# MK64.net
KiCad netlist of a schematic drawn in Altium Designer
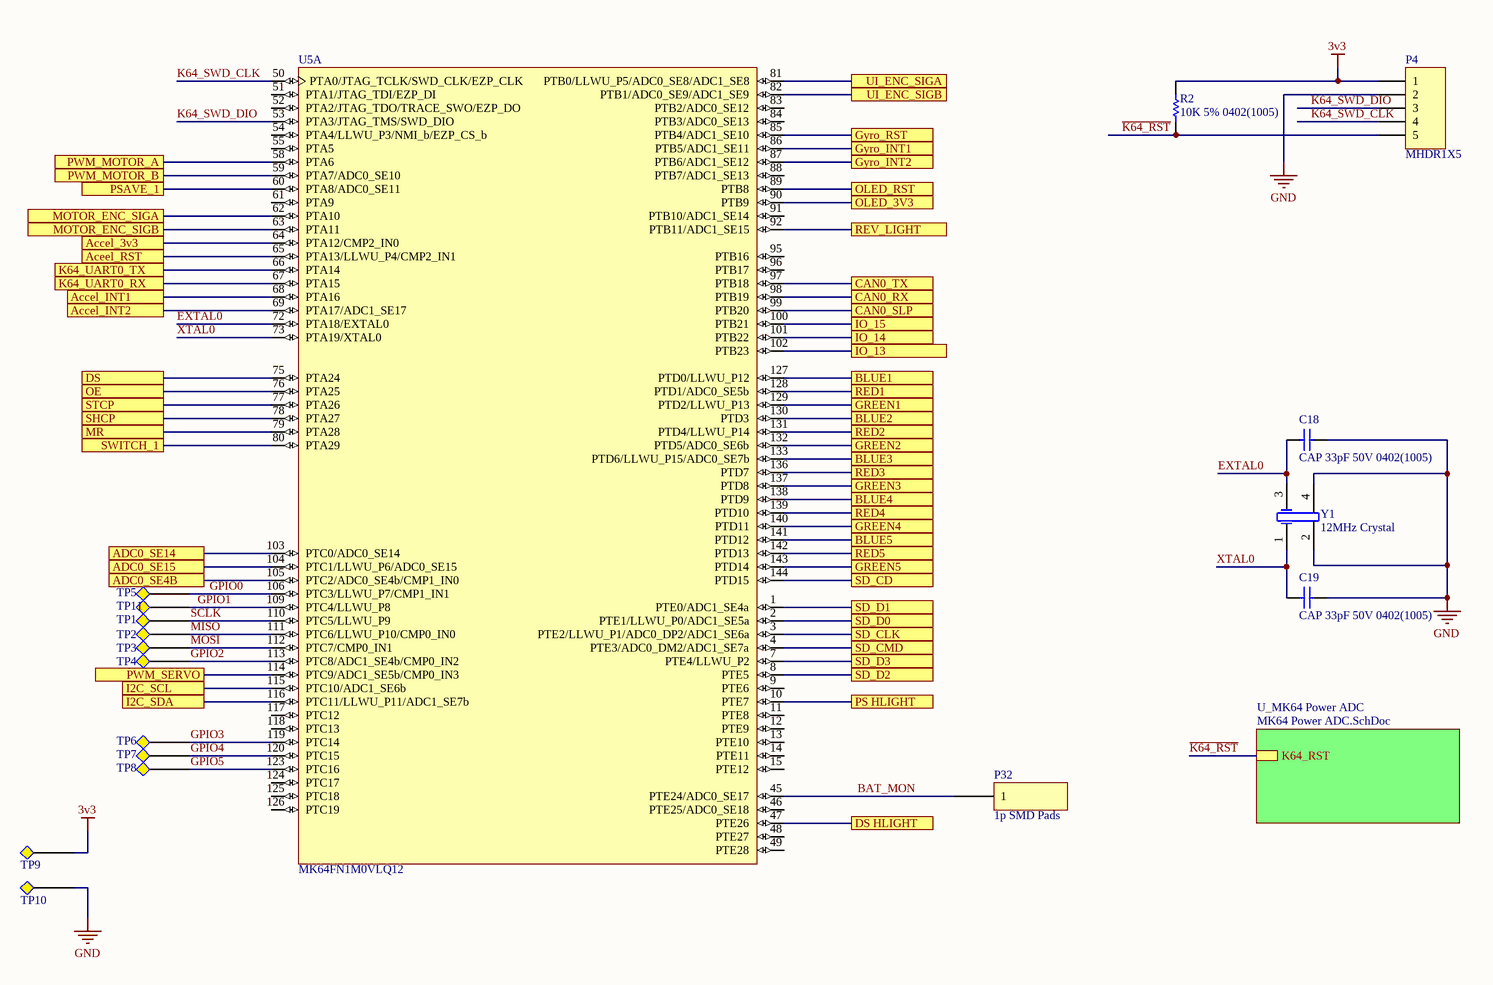
[diagram p0: MK64.SchDoc]

(export (version "E")
  (design (tool "Eeschema 10.0.6"))
  (components
    (comp (ref "C18")
      (value "CAP 33pF 50V 0402(1005)")
      (footprint "CAPC0402(1005)60_N")
      (description "CAP 33pF 50V ±5% 0402 (1005 Metric) Thickness 0.6mm SMD")
      (fields (field (name "TOLERANCE") "Â±5%"))
      (libsource (lib "Altium Content Vault") (part "CAP"))
    )
    (comp (ref "C19")
      (value "CAP 33pF 50V 0402(1005)")
      (footprint "CAPC0402(1005)60_N")
      (description "CAP 33pF 50V ±5% 0402 (1005 Metric) Thickness 0.6mm SMD")
      (fields (field (name "TOLERANCE") "Â±5%"))
      (libsource (lib "Altium Content Vault") (part "CAP"))
    )
    (comp (ref "P4")
      (value "MHDR1X5")
      (footprint "MHDR1X5")
      (description "Header, 5-Pin")
      (fields (field (name "PUBLISHER") "Altium Limited"))
      (libsource (lib "Miscellaneous Connectors") (part "MHDR1X5"))
    )
    (comp (ref "P32")
      (value "1p SMD Pads")
      (footprint "1p SMD pad")
      (libsource (lib "parts") (part "1p SMD"))
    )
    (comp (ref "R2")
      (value "10K 5% 0402(1005)")
      (footprint "RESC0402(1005)_N")
      (description "10K 0.063W 5% 0402 (1005 Metric)  SMD")
      (fields (field (name "TOLERANCE") "5 %") (field (name "POWER") "0.063 W"))
      (libsource (lib "Altium Content Vault") (part "RES"))
    )
    (comp (ref "TP1") (value "Test Point") (footprint "TP") (libsource (lib "parts") (part "TP")))
    (comp (ref "TP2") (value "Test Point") (footprint "TP") (libsource (lib "parts") (part "TP")))
    (comp (ref "TP3") (value "Test Point") (footprint "TP") (libsource (lib "parts") (part "TP")))
    (comp (ref "TP4") (value "Test Point") (footprint "TP") (libsource (lib "parts") (part "TP")))
    (comp (ref "TP5") (value "Test Point") (footprint "TP") (libsource (lib "parts") (part "TP")))
    (comp (ref "TP6") (value "Test Point") (footprint "TP") (libsource (lib "parts") (part "TP")))
    (comp (ref "TP7") (value "Test Point") (footprint "TP") (libsource (lib "parts") (part "TP")))
    (comp (ref "TP8") (value "Test Point") (footprint "TP") (libsource (lib "parts") (part "TP")))
    (comp (ref "TP9") (value "Test Point") (footprint "TP") (libsource (lib "parts") (part "TP")))
    (comp (ref "TP10") (value "Test Point") (footprint "TP") (libsource (lib "parts") (part "TP")))
    (comp (ref "TP11") (value "Test Point") (footprint "TP") (libsource (lib "parts") (part "TP")))
    (comp (ref "U5")
      (value "MK64FN1M0VLQ12")
      (footprint "918-03_N")
      (fields (field (name "MANUFACTURER") "Freescale Semiconductor"))
      (libsource (lib "Altium Content Vault") (part "FRES-MK64FX512VLQ12-144"))
    )
    (comp (ref "Y1")
      (value "12MHz Crystal")
      (footprint "DFN155P250X80-4N")
      (description "CRYSTAL 12.0000MHZ 20PF SMD 3.20x2.50")
      (fields (field (name "PUBLISHER") "Altium Limited"))
      (libsource (lib "parts") (part "403C11E16M00000"))
    )
  )
  (nets
    (net (code "1") (name "/ADC0_SE4B") (class "Default")
      (node (ref "U5") (pin "105") (pinfunction "PTC2/ADC0_SE4b/CMP1_IN0_105") (pintype "bidirectional"))
    )
    (net (code "2") (name "/ADC0_SE14") (class "Default")
      (node (ref "U5") (pin "103") (pinfunction "PTC0/ADC0_SE14_103") (pintype "bidirectional"))
    )
    (net (code "3") (name "/ADC0_SE15") (class "Default")
      (node (ref "U5") (pin "104") (pinfunction "PTC1/LLWU_P6/ADC0_SE15_104") (pintype "bidirectional"))
    )
    (net (code "4") (name "/Accel_3v3") (class "Default")
      (node (ref "U5") (pin "64") (pinfunction "PTA12/CMP2_IN0_64") (pintype "bidirectional"))
    )
    (net (code "5") (name "/Accel_INT1") (class "Default")
      (node (ref "U5") (pin "68") (pinfunction "PTA16_68") (pintype "bidirectional"))
    )
    (net (code "6") (name "/Accel_INT2") (class "Default")
      (node (ref "U5") (pin "69") (pinfunction "PTA17/ADC1_SE17_69") (pintype "bidirectional"))
    )
    (net (code "7") (name "/Aceel_RST") (class "Default")
      (node (ref "U5") (pin "65") (pinfunction "PTA13/LLWU_P4/CMP2_IN1_65") (pintype "bidirectional"))
    )
    (net (code "8") (name "/BAT_MON") (class "Default")
      (node (ref "P32") (pin "1") (pinfunction "1_1") (pintype "passive"))
      (node (ref "U5") (pin "45") (pinfunction "PTE24/ADC0_SE17_45") (pintype "bidirectional"))
    )
    (net (code "9") (name "/BLUE1") (class "Default")
      (node (ref "U5") (pin "127") (pinfunction "PTD0/LLWU_P12_127") (pintype "bidirectional"))
    )
    (net (code "10") (name "/BLUE2") (class "Default")
      (node (ref "U5") (pin "130") (pinfunction "PTD3_130") (pintype "bidirectional"))
    )
    (net (code "11") (name "/BLUE3") (class "Default")
      (node (ref "U5") (pin "133") (pinfunction "PTD6/LLWU_P15/ADC0_SE7b_133") (pintype "bidirectional"))
    )
    (net (code "12") (name "/BLUE4") (class "Default")
      (node (ref "U5") (pin "138") (pinfunction "PTD9_138") (pintype "bidirectional"))
    )
    (net (code "13") (name "/BLUE5") (class "Default")
      (node (ref "U5") (pin "141") (pinfunction "PTD12_141") (pintype "bidirectional"))
    )
    (net (code "14") (name "/CAN0_RX") (class "Default")
      (node (ref "U5") (pin "98") (pinfunction "PTB19_98") (pintype "bidirectional"))
    )
    (net (code "15") (name "/CAN0_SLP") (class "Default")
      (node (ref "U5") (pin "99") (pinfunction "PTB20_99") (pintype "bidirectional"))
    )
    (net (code "16") (name "/CAN0_TX") (class "Default")
      (node (ref "U5") (pin "97") (pinfunction "PTB18_97") (pintype "bidirectional"))
    )
    (net (code "17") (name "/DS") (class "Default")
      (node (ref "U5") (pin "75") (pinfunction "PTA24_75") (pintype "bidirectional"))
    )
    (net (code "18") (name "/DS HLIGHT") (class "Default")
      (node (ref "U5") (pin "47") (pinfunction "PTE26_47") (pintype "bidirectional"))
    )
    (net (code "19") (name "/EXTAL0") (class "Default")
      (node (ref "C18") (pin "1") (pinfunction "1_1") (pintype "passive"))
      (node (ref "U5") (pin "72") (pinfunction "PTA18/EXTAL0_72") (pintype "bidirectional"))
      (node (ref "Y1") (pin "3") (pinfunction "OSC2_3") (pintype "passive"))
    )
    (net (code "20") (name "/GPIO0") (class "Default")
      (node (ref "TP5") (pin "1") (pinfunction "1_1") (pintype "passive"))
      (node (ref "U5") (pin "106") (pinfunction "PTC3/LLWU_P7/CMP1_IN1_106") (pintype "bidirectional"))
    )
    (net (code "21") (name "/GPIO1") (class "Default")
      (node (ref "TP11") (pin "1") (pinfunction "1_1") (pintype "passive"))
      (node (ref "U5") (pin "109") (pinfunction "PTC4/LLWU_P8_109") (pintype "bidirectional"))
    )
    (net (code "22") (name "/GPIO2") (class "Default")
      (node (ref "TP4") (pin "1") (pinfunction "1_1") (pintype "passive"))
      (node (ref "U5") (pin "113") (pinfunction "PTC8/ADC1_SE4b/CMP0_IN2_113") (pintype "bidirectional"))
    )
    (net (code "23") (name "/GPIO3") (class "Default")
      (node (ref "TP6") (pin "1") (pinfunction "1_1") (pintype "passive"))
      (node (ref "U5") (pin "119") (pinfunction "PTC14_119") (pintype "bidirectional"))
    )
    (net (code "24") (name "/GPIO4") (class "Default")
      (node (ref "TP7") (pin "1") (pinfunction "1_1") (pintype "passive"))
      (node (ref "U5") (pin "120") (pinfunction "PTC15_120") (pintype "bidirectional"))
    )
    (net (code "25") (name "/GPIO5") (class "Default")
      (node (ref "TP8") (pin "1") (pinfunction "1_1") (pintype "passive"))
      (node (ref "U5") (pin "123") (pinfunction "PTC16_123") (pintype "bidirectional"))
    )
    (net (code "26") (name "/GREEN1") (class "Default")
      (node (ref "U5") (pin "129") (pinfunction "PTD2/LLWU_P13_129") (pintype "bidirectional"))
    )
    (net (code "27") (name "/GREEN2") (class "Default")
      (node (ref "U5") (pin "132") (pinfunction "PTD5/ADC0_SE6b_132") (pintype "bidirectional"))
    )
    (net (code "28") (name "/GREEN3") (class "Default")
      (node (ref "U5") (pin "137") (pinfunction "PTD8_137") (pintype "bidirectional"))
    )
    (net (code "29") (name "/GREEN4") (class "Default")
      (node (ref "U5") (pin "140") (pinfunction "PTD11_140") (pintype "bidirectional"))
    )
    (net (code "30") (name "/GREEN5") (class "Default")
      (node (ref "U5") (pin "143") (pinfunction "PTD14_143") (pintype "bidirectional"))
    )
    (net (code "31") (name "/Gyro_INT1") (class "Default")
      (node (ref "U5") (pin "86") (pinfunction "PTB5/ADC1_SE11_86") (pintype "bidirectional"))
    )
    (net (code "32") (name "/Gyro_INT2") (class "Default")
      (node (ref "U5") (pin "87") (pinfunction "PTB6/ADC1_SE12_87") (pintype "bidirectional"))
    )
    (net (code "33") (name "/Gyro_RST") (class "Default")
      (node (ref "U5") (pin "85") (pinfunction "PTB4/ADC1_SE10_85") (pintype "bidirectional"))
    )
    (net (code "34") (name "/I2C_SCL") (class "Default")
      (node (ref "U5") (pin "115") (pinfunction "PTC10/ADC1_SE6b_115") (pintype "bidirectional"))
    )
    (net (code "35") (name "/I2C_SDA") (class "Default")
      (node (ref "U5") (pin "116") (pinfunction "PTC11/LLWU_P11/ADC1_SE7b_116") (pintype "bidirectional"))
    )
    (net (code "36") (name "/IO_13") (class "Default")
      (node (ref "U5") (pin "102") (pinfunction "PTB23_102") (pintype "bidirectional"))
    )
    (net (code "37") (name "/IO_14") (class "Default")
      (node (ref "U5") (pin "101") (pinfunction "PTB22_101") (pintype "bidirectional"))
    )
    (net (code "38") (name "/IO_15") (class "Default")
      (node (ref "U5") (pin "100") (pinfunction "PTB21_100") (pintype "bidirectional"))
    )
    (net (code "39") (name "/K64_RST") (class "Default")
      (node (ref "P4") (pin "5") (pinfunction "5_5") (pintype "passive"))
      (node (ref "R2") (pin "1") (pinfunction "1_1") (pintype "passive"))
    )
    (net (code "40") (name "/K64_SWD_CLK") (class "Default")
      (node (ref "P4") (pin "4") (pinfunction "4_4") (pintype "passive"))
      (node (ref "U5") (pin "50") (pinfunction "PTA0/JTAG_TCLK/SWD_CLK/EZP_CLK_50") (pintype "bidirectional"))
    )
    (net (code "41") (name "/K64_SWD_DIO") (class "Default")
      (node (ref "P4") (pin "3") (pinfunction "3_3") (pintype "passive"))
      (node (ref "U5") (pin "53") (pinfunction "PTA3/JTAG_TMS/SWD_DIO_53") (pintype "bidirectional"))
    )
    (net (code "42") (name "/K64_UART0_RX") (class "Default")
      (node (ref "U5") (pin "67") (pinfunction "PTA15_67") (pintype "bidirectional"))
    )
    (net (code "43") (name "/K64_UART0_TX") (class "Default")
      (node (ref "U5") (pin "66") (pinfunction "PTA14_66") (pintype "bidirectional"))
    )
    (net (code "44") (name "/MISO") (class "Default")
      (node (ref "TP2") (pin "1") (pinfunction "1_1") (pintype "passive"))
      (node (ref "U5") (pin "111") (pinfunction "PTC6/LLWU_P10/CMP0_IN0_111") (pintype "bidirectional"))
    )
    (net (code "45") (name "/MOSI") (class "Default")
      (node (ref "TP3") (pin "1") (pinfunction "1_1") (pintype "passive"))
      (node (ref "U5") (pin "112") (pinfunction "PTC7/CMP0_IN1_112") (pintype "bidirectional"))
    )
    (net (code "46") (name "/MOTOR_ENC_SIGA") (class "Default")
      (node (ref "U5") (pin "62") (pinfunction "PTA10_62") (pintype "bidirectional"))
    )
    (net (code "47") (name "/MOTOR_ENC_SIGB") (class "Default")
      (node (ref "U5") (pin "63") (pinfunction "PTA11_63") (pintype "bidirectional"))
    )
    (net (code "48") (name "/MR") (class "Default")
      (node (ref "U5") (pin "79") (pinfunction "PTA28_79") (pintype "bidirectional"))
    )
    (net (code "49") (name "/OE") (class "Default")
      (node (ref "U5") (pin "76") (pinfunction "PTA25_76") (pintype "bidirectional"))
    )
    (net (code "50") (name "/OLED_3V3") (class "Default")
      (node (ref "U5") (pin "90") (pinfunction "PTB9_90") (pintype "bidirectional"))
    )
    (net (code "51") (name "/OLED_RST") (class "Default")
      (node (ref "U5") (pin "89") (pinfunction "PTB8_89") (pintype "bidirectional"))
    )
    (net (code "52") (name "/PS HLIGHT") (class "Default")
      (node (ref "U5") (pin "10") (pinfunction "PTE7_10") (pintype "bidirectional"))
    )
    (net (code "53") (name "/PSAVE_1") (class "Default")
      (node (ref "U5") (pin "60") (pinfunction "PTA8/ADC0_SE11_60") (pintype "bidirectional"))
    )
    (net (code "54") (name "/PWM_MOTOR_A") (class "Default")
      (node (ref "U5") (pin "58") (pinfunction "PTA6_58") (pintype "bidirectional"))
    )
    (net (code "55") (name "/PWM_MOTOR_B") (class "Default")
      (node (ref "U5") (pin "59") (pinfunction "PTA7/ADC0_SE10_59") (pintype "bidirectional"))
    )
    (net (code "56") (name "/PWM_SERVO") (class "Default")
      (node (ref "U5") (pin "114") (pinfunction "PTC9/ADC1_SE5b/CMP0_IN3_114") (pintype "bidirectional"))
    )
    (net (code "57") (name "/RED1") (class "Default")
      (node (ref "U5") (pin "128") (pinfunction "PTD1/ADC0_SE5b_128") (pintype "bidirectional"))
    )
    (net (code "58") (name "/RED2") (class "Default")
      (node (ref "U5") (pin "131") (pinfunction "PTD4/LLWU_P14_131") (pintype "bidirectional"))
    )
    (net (code "59") (name "/RED3") (class "Default")
      (node (ref "U5") (pin "136") (pinfunction "PTD7_136") (pintype "bidirectional"))
    )
    (net (code "60") (name "/RED4") (class "Default")
      (node (ref "U5") (pin "139") (pinfunction "PTD10_139") (pintype "bidirectional"))
    )
    (net (code "61") (name "/RED5") (class "Default")
      (node (ref "U5") (pin "142") (pinfunction "PTD13_142") (pintype "bidirectional"))
    )
    (net (code "62") (name "/REV_LIGHT") (class "Default")
      (node (ref "U5") (pin "92") (pinfunction "PTB11/ADC1_SE15_92") (pintype "bidirectional"))
    )
    (net (code "63") (name "/SCLK") (class "Default")
      (node (ref "TP1") (pin "1") (pinfunction "1_1") (pintype "passive"))
      (node (ref "U5") (pin "110") (pinfunction "PTC5/LLWU_P9_110") (pintype "bidirectional"))
    )
    (net (code "64") (name "/SD_CD") (class "Default")
      (node (ref "U5") (pin "144") (pinfunction "PTD15_144") (pintype "bidirectional"))
    )
    (net (code "65") (name "/SD_CLK") (class "Default")
      (node (ref "U5") (pin "3") (pinfunction "PTE2/LLWU_P1/ADC0_DP2/ADC1_SE6a_3") (pintype "bidirectional"))
    )
    (net (code "66") (name "/SD_CMD") (class "Default")
      (node (ref "U5") (pin "4") (pinfunction "PTE3/ADC0_DM2/ADC1_SE7a_4") (pintype "bidirectional"))
    )
    (net (code "67") (name "/SD_D0") (class "Default")
      (node (ref "U5") (pin "2") (pinfunction "PTE1/LLWU_P0/ADC1_SE5a_2") (pintype "bidirectional"))
    )
    (net (code "68") (name "/SD_D1") (class "Default")
      (node (ref "U5") (pin "1") (pinfunction "PTE0/ADC1_SE4a_1") (pintype "bidirectional"))
    )
    (net (code "69") (name "/SD_D2") (class "Default")
      (node (ref "U5") (pin "8") (pinfunction "PTE5_8") (pintype "bidirectional"))
    )
    (net (code "70") (name "/SD_D3") (class "Default")
      (node (ref "U5") (pin "7") (pinfunction "PTE4/LLWU_P2_7") (pintype "bidirectional"))
    )
    (net (code "71") (name "/SHCP") (class "Default")
      (node (ref "U5") (pin "78") (pinfunction "PTA27_78") (pintype "bidirectional"))
    )
    (net (code "72") (name "/STCP") (class "Default")
      (node (ref "U5") (pin "77") (pinfunction "PTA26_77") (pintype "bidirectional"))
    )
    (net (code "73") (name "/SWITCH_1") (class "Default")
      (node (ref "U5") (pin "80") (pinfunction "PTA29_80") (pintype "bidirectional"))
    )
    (net (code "74") (name "/UI_ENC_SIGA") (class "Default")
      (node (ref "U5") (pin "81") (pinfunction "PTB0/LLWU_P5/ADC0_SE8/ADC1_SE8_81") (pintype "bidirectional"))
    )
    (net (code "75") (name "/UI_ENC_SIGB") (class "Default")
      (node (ref "U5") (pin "82") (pinfunction "PTB1/ADC0_SE9/ADC1_SE9_82") (pintype "bidirectional"))
    )
    (net (code "76") (name "/XTAL0") (class "Default")
      (node (ref "C19") (pin "1") (pinfunction "1_1") (pintype "passive"))
      (node (ref "U5") (pin "73") (pinfunction "PTA19/XTAL0_73") (pintype "bidirectional"))
      (node (ref "Y1") (pin "1") (pinfunction "OSC1_1") (pintype "passive"))
    )
    (net (code "77") (name "3v3") (class "Default")
      (node (ref "P4") (pin "1") (pinfunction "1_1") (pintype "passive"))
      (node (ref "R2") (pin "2") (pinfunction "2_2") (pintype "passive"))
      (node (ref "TP9") (pin "1") (pinfunction "1_1") (pintype "passive"))
    )
    (net (code "78") (name "GND") (class "Default")
      (node (ref "C18") (pin "2") (pinfunction "2_2") (pintype "passive"))
      (node (ref "C19") (pin "2") (pinfunction "2_2") (pintype "passive"))
      (node (ref "P4") (pin "2") (pinfunction "2_2") (pintype "passive"))
      (node (ref "TP10") (pin "1") (pinfunction "1_1") (pintype "passive"))
      (node (ref "Y1") (pin "2") (pinfunction "GND_2") (pintype "passive"))
      (node (ref "Y1") (pin "4") (pinfunction "GND_4") (pintype "passive"))
    )
    (net (code "79") (name "unconnected-(U5A-PTA1{slash}JTAG_TDI{slash}EZP_DI-Pad51)") (class "Default")
      (node (ref "U5") (pin "51") (pinfunction "PTA1/JTAG_TDI/EZP_DI_51") (pintype "bidirectional"))
    )
    (net (code "80") (name "unconnected-(U5A-PTA2{slash}JTAG_TDO{slash}TRACE_SWO{slash}EZP_DO-Pad52)") (class "Default")
      (node (ref "U5") (pin "52") (pinfunction "PTA2/JTAG_TDO/TRACE_SWO/EZP_DO_52") (pintype "bidirectional"))
    )
    (net (code "81") (name "unconnected-(U5A-PTA4{slash}LLWU_P3{slash}NMI_b{slash}EZP_CS_b-Pad54)") (class "Default")
      (node (ref "U5") (pin "54") (pinfunction "PTA4/LLWU_P3/NMI_b/EZP_CS_b_54") (pintype "bidirectional"))
    )
    (net (code "82") (name "unconnected-(U5A-PTA5-Pad55)") (class "Default")
      (node (ref "U5") (pin "55") (pinfunction "PTA5_55") (pintype "bidirectional"))
    )
    (net (code "83") (name "unconnected-(U5A-PTA9-Pad61)") (class "Default")
      (node (ref "U5") (pin "61") (pinfunction "PTA9_61") (pintype "bidirectional"))
    )
    (net (code "84") (name "unconnected-(U5A-PTB2{slash}ADC0_SE12-Pad83)") (class "Default")
      (node (ref "U5") (pin "83") (pinfunction "PTB2/ADC0_SE12_83") (pintype "bidirectional"))
    )
    (net (code "85") (name "unconnected-(U5A-PTB3{slash}ADC0_SE13-Pad84)") (class "Default")
      (node (ref "U5") (pin "84") (pinfunction "PTB3/ADC0_SE13_84") (pintype "bidirectional"))
    )
    (net (code "86") (name "unconnected-(U5A-PTB7{slash}ADC1_SE13-Pad88)") (class "Default")
      (node (ref "U5") (pin "88") (pinfunction "PTB7/ADC1_SE13_88") (pintype "bidirectional"))
    )
    (net (code "87") (name "unconnected-(U5A-PTB10{slash}ADC1_SE14-Pad91)") (class "Default")
      (node (ref "U5") (pin "91") (pinfunction "PTB10/ADC1_SE14_91") (pintype "bidirectional"))
    )
    (net (code "88") (name "unconnected-(U5A-PTB16-Pad95)") (class "Default")
      (node (ref "U5") (pin "95") (pinfunction "PTB16_95") (pintype "bidirectional"))
    )
    (net (code "89") (name "unconnected-(U5A-PTB17-Pad96)") (class "Default")
      (node (ref "U5") (pin "96") (pinfunction "PTB17_96") (pintype "bidirectional"))
    )
    (net (code "90") (name "unconnected-(U5A-PTC12-Pad117)") (class "Default")
      (node (ref "U5") (pin "117") (pinfunction "PTC12_117") (pintype "bidirectional"))
    )
    (net (code "91") (name "unconnected-(U5A-PTC13-Pad118)") (class "Default")
      (node (ref "U5") (pin "118") (pinfunction "PTC13_118") (pintype "bidirectional"))
    )
    (net (code "92") (name "unconnected-(U5A-PTC17-Pad124)") (class "Default")
      (node (ref "U5") (pin "124") (pinfunction "PTC17_124") (pintype "bidirectional"))
    )
    (net (code "93") (name "unconnected-(U5A-PTC18-Pad125)") (class "Default")
      (node (ref "U5") (pin "125") (pinfunction "PTC18_125") (pintype "bidirectional"))
    )
    (net (code "94") (name "unconnected-(U5A-PTC19-Pad126)") (class "Default")
      (node (ref "U5") (pin "126") (pinfunction "PTC19_126") (pintype "bidirectional"))
    )
    (net (code "95") (name "unconnected-(U5A-PTE6-Pad9)") (class "Default")
      (node (ref "U5") (pin "9") (pinfunction "PTE6_9") (pintype "bidirectional"))
    )
    (net (code "96") (name "unconnected-(U5A-PTE8-Pad11)") (class "Default")
      (node (ref "U5") (pin "11") (pinfunction "PTE8_11") (pintype "bidirectional"))
    )
    (net (code "97") (name "unconnected-(U5A-PTE9-Pad12)") (class "Default")
      (node (ref "U5") (pin "12") (pinfunction "PTE9_12") (pintype "bidirectional"))
    )
    (net (code "98") (name "unconnected-(U5A-PTE10-Pad13)") (class "Default")
      (node (ref "U5") (pin "13") (pinfunction "PTE10_13") (pintype "bidirectional"))
    )
    (net (code "99") (name "unconnected-(U5A-PTE11-Pad14)") (class "Default")
      (node (ref "U5") (pin "14") (pinfunction "PTE11_14") (pintype "bidirectional"))
    )
    (net (code "100") (name "unconnected-(U5A-PTE12-Pad15)") (class "Default")
      (node (ref "U5") (pin "15") (pinfunction "PTE12_15") (pintype "bidirectional"))
    )
    (net (code "101") (name "unconnected-(U5A-PTE25{slash}ADC0_SE18-Pad46)") (class "Default")
      (node (ref "U5") (pin "46") (pinfunction "PTE25/ADC0_SE18_46") (pintype "bidirectional"))
    )
    (net (code "102") (name "unconnected-(U5A-PTE27-Pad48)") (class "Default")
      (node (ref "U5") (pin "48") (pinfunction "PTE27_48") (pintype "bidirectional"))
    )
    (net (code "103") (name "unconnected-(U5A-PTE28-Pad49)") (class "Default")
      (node (ref "U5") (pin "49") (pinfunction "PTE28_49") (pintype "bidirectional"))
    )
  )
)
